# Mini_Keyboard_EasyEDA.net
KiCad netlist of a schematic drawn in EasyEDA
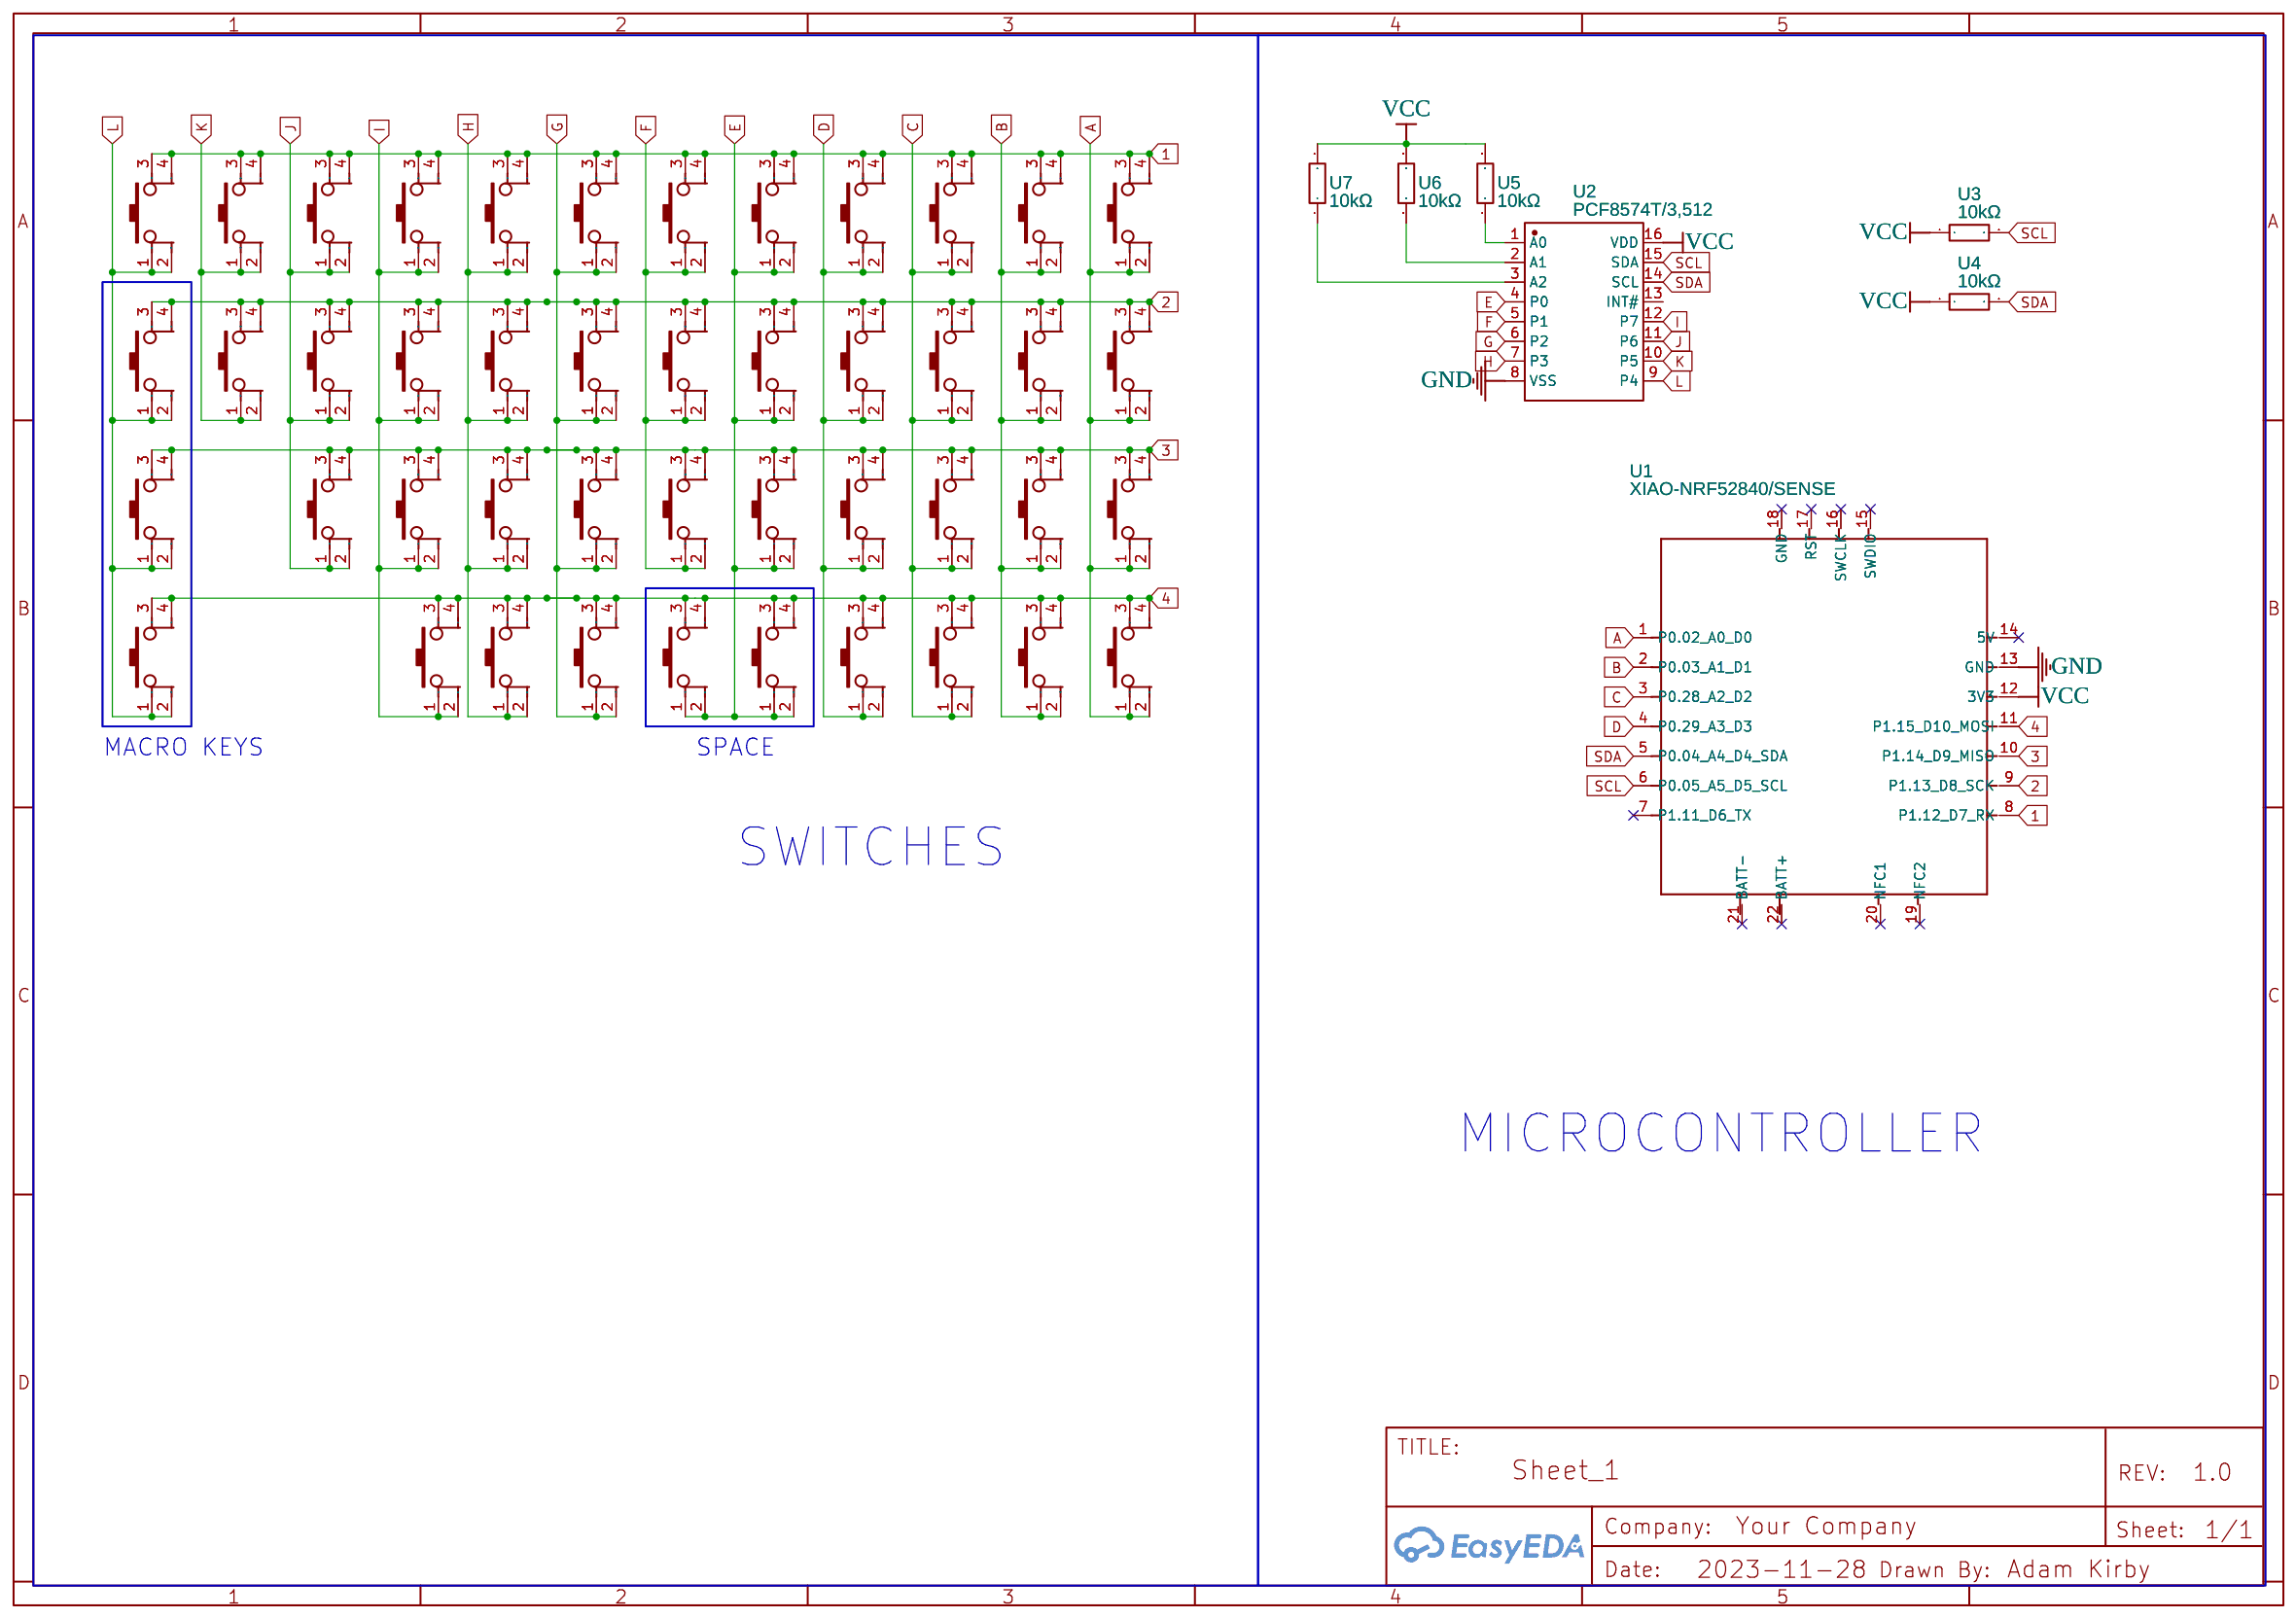
[diagram p0: schematic sheet]

(export (version "E")
  (design (tool "Eeschema 10.0.6"))
  (components
    (comp (ref "ESC")
      (value "Switch-SMD-6x6x11")
      (fields (field (name "Manufacturer Part") "Switch6*6*11") (field (name "Manufacturer") "BBJ"))
      (libsource (lib "") (part "Switch-SMD-6x6x11_1"))
    )
    (comp (ref "MAC1")
      (value "Switch-SMD-6x6x11")
      (fields (field (name "Manufacturer Part") "Switch6*6*11") (field (name "Manufacturer") "BBJ"))
      (libsource (lib "") (part "Switch-SMD-6x6x11_2"))
    )
    (comp (ref "MAC2")
      (value "Switch-SMD-6x6x11")
      (fields (field (name "Manufacturer Part") "Switch6*6*11") (field (name "Manufacturer") "BBJ"))
      (libsource (lib "") (part "Switch-SMD-6x6x11_2"))
    )
    (comp (ref "MAC3")
      (value "Switch-SMD-6x6x11")
      (fields (field (name "Manufacturer Part") "Switch6*6*11") (field (name "Manufacturer") "BBJ"))
      (libsource (lib "") (part "Switch-SMD-6x6x11_2"))
    )
    (comp (ref "SW1")
      (value "Switch-SMD-6x6x11")
      (fields (field (name "Manufacturer Part") "Switch6*6*11") (field (name "Manufacturer") "BBJ"))
      (libsource (lib "") (part "Switch-SMD-6x6x11"))
    )
    (comp (ref "SW2")
      (value "Switch-SMD-6x6x11")
      (fields (field (name "Manufacturer Part") "Switch6*6*11") (field (name "Manufacturer") "BBJ"))
      (libsource (lib "") (part "Switch-SMD-6x6x11"))
    )
    (comp (ref "SW3")
      (value "Switch-SMD-6x6x11")
      (fields (field (name "Manufacturer Part") "Switch6*6*11") (field (name "Manufacturer") "BBJ"))
      (libsource (lib "") (part "Switch-SMD-6x6x11"))
    )
    (comp (ref "SW4")
      (value "Switch-SMD-6x6x11")
      (fields (field (name "Manufacturer Part") "Switch6*6*11") (field (name "Manufacturer") "BBJ"))
      (libsource (lib "") (part "Switch-SMD-6x6x11"))
    )
    (comp (ref "SW5")
      (value "Switch-SMD-6x6x11")
      (fields (field (name "Manufacturer Part") "Switch6*6*11") (field (name "Manufacturer") "BBJ"))
      (libsource (lib "") (part "Switch-SMD-6x6x11"))
    )
    (comp (ref "SW6")
      (value "Switch-SMD-6x6x11")
      (fields (field (name "Manufacturer Part") "Switch6*6*11") (field (name "Manufacturer") "BBJ"))
      (libsource (lib "") (part "Switch-SMD-6x6x11"))
    )
    (comp (ref "SW7")
      (value "Switch-SMD-6x6x11")
      (fields (field (name "Manufacturer Part") "Switch6*6*11") (field (name "Manufacturer") "BBJ"))
      (libsource (lib "") (part "Switch-SMD-6x6x11"))
    )
    (comp (ref "SW8")
      (value "Switch-SMD-6x6x11")
      (fields (field (name "Manufacturer Part") "Switch6*6*11") (field (name "Manufacturer") "BBJ"))
      (libsource (lib "") (part "Switch-SMD-6x6x11"))
    )
    (comp (ref "SW9")
      (value "Switch-SMD-6x6x11")
      (fields (field (name "Manufacturer Part") "Switch6*6*11") (field (name "Manufacturer") "BBJ"))
      (libsource (lib "") (part "Switch-SMD-6x6x11"))
    )
    (comp (ref "SW10")
      (value "Switch-SMD-6x6x11")
      (fields (field (name "Manufacturer Part") "Switch6*6*11") (field (name "Manufacturer") "BBJ"))
      (libsource (lib "") (part "Switch-SMD-6x6x11"))
    )
    (comp (ref "SW11")
      (value "Switch-SMD-6x6x11")
      (fields (field (name "Manufacturer Part") "Switch6*6*11") (field (name "Manufacturer") "BBJ"))
      (libsource (lib "") (part "Switch-SMD-6x6x11"))
    )
    (comp (ref "SW12")
      (value "Switch-SMD-6x6x11")
      (fields (field (name "Manufacturer Part") "Switch6*6*11") (field (name "Manufacturer") "BBJ"))
      (libsource (lib "") (part "Switch-SMD-6x6x11"))
    )
    (comp (ref "SW13")
      (value "Switch-SMD-6x6x11")
      (fields (field (name "Manufacturer Part") "Switch6*6*11") (field (name "Manufacturer") "BBJ"))
      (libsource (lib "") (part "Switch-SMD-6x6x11"))
    )
    (comp (ref "SW14")
      (value "Switch-SMD-6x6x11")
      (fields (field (name "Manufacturer Part") "Switch6*6*11") (field (name "Manufacturer") "BBJ"))
      (libsource (lib "") (part "Switch-SMD-6x6x11"))
    )
    (comp (ref "SW15")
      (value "Switch-SMD-6x6x11")
      (fields (field (name "Manufacturer Part") "Switch6*6*11") (field (name "Manufacturer") "BBJ"))
      (libsource (lib "") (part "Switch-SMD-6x6x11"))
    )
    (comp (ref "SW16")
      (value "Switch-SMD-6x6x11")
      (fields (field (name "Manufacturer Part") "Switch6*6*11") (field (name "Manufacturer") "BBJ"))
      (libsource (lib "") (part "Switch-SMD-6x6x11"))
    )
    (comp (ref "SW17")
      (value "Switch-SMD-6x6x11")
      (fields (field (name "Manufacturer Part") "Switch6*6*11") (field (name "Manufacturer") "BBJ"))
      (libsource (lib "") (part "Switch-SMD-6x6x11"))
    )
    (comp (ref "SW18")
      (value "Switch-SMD-6x6x11")
      (fields (field (name "Manufacturer Part") "Switch6*6*11") (field (name "Manufacturer") "BBJ"))
      (libsource (lib "") (part "Switch-SMD-6x6x11"))
    )
    (comp (ref "SW19")
      (value "Switch-SMD-6x6x11")
      (fields (field (name "Manufacturer Part") "Switch6*6*11") (field (name "Manufacturer") "BBJ"))
      (libsource (lib "") (part "Switch-SMD-6x6x11"))
    )
    (comp (ref "SW20")
      (value "Switch-SMD-6x6x11")
      (fields (field (name "Manufacturer Part") "Switch6*6*11") (field (name "Manufacturer") "BBJ"))
      (libsource (lib "") (part "Switch-SMD-6x6x11"))
    )
    (comp (ref "SW21")
      (value "Switch-SMD-6x6x11")
      (fields (field (name "Manufacturer Part") "Switch6*6*11") (field (name "Manufacturer") "BBJ"))
      (libsource (lib "") (part "Switch-SMD-6x6x11"))
    )
    (comp (ref "SW22")
      (value "Switch-SMD-6x6x11")
      (fields (field (name "Manufacturer Part") "Switch6*6*11") (field (name "Manufacturer") "BBJ"))
      (libsource (lib "") (part "Switch-SMD-6x6x11"))
    )
    (comp (ref "SW23")
      (value "Switch-SMD-6x6x11")
      (fields (field (name "Manufacturer Part") "Switch6*6*11") (field (name "Manufacturer") "BBJ"))
      (libsource (lib "") (part "Switch-SMD-6x6x11"))
    )
    (comp (ref "SW24")
      (value "Switch-SMD-6x6x11")
      (fields (field (name "Manufacturer Part") "Switch6*6*11") (field (name "Manufacturer") "BBJ"))
      (libsource (lib "") (part "Switch-SMD-6x6x11"))
    )
    (comp (ref "SW25")
      (value "Switch-SMD-6x6x11")
      (fields (field (name "Manufacturer Part") "Switch6*6*11") (field (name "Manufacturer") "BBJ"))
      (libsource (lib "") (part "Switch-SMD-6x6x11"))
    )
    (comp (ref "SW27")
      (value "Switch-SMD-6x6x11")
      (fields (field (name "Manufacturer Part") "Switch6*6*11") (field (name "Manufacturer") "BBJ"))
      (libsource (lib "") (part "Switch-SMD-6x6x11"))
    )
    (comp (ref "SW28")
      (value "Switch-SMD-6x6x11")
      (fields (field (name "Manufacturer Part") "Switch6*6*11") (field (name "Manufacturer") "BBJ"))
      (libsource (lib "") (part "Switch-SMD-6x6x11"))
    )
    (comp (ref "SW29")
      (value "Switch-SMD-6x6x11")
      (fields (field (name "Manufacturer Part") "Switch6*6*11") (field (name "Manufacturer") "BBJ"))
      (libsource (lib "") (part "Switch-SMD-6x6x11"))
    )
    (comp (ref "SW30")
      (value "Switch-SMD-6x6x11")
      (fields (field (name "Manufacturer Part") "Switch6*6*11") (field (name "Manufacturer") "BBJ"))
      (libsource (lib "") (part "Switch-SMD-6x6x11"))
    )
    (comp (ref "SW31")
      (value "Switch-SMD-6x6x11")
      (fields (field (name "Manufacturer Part") "Switch6*6*11") (field (name "Manufacturer") "BBJ"))
      (libsource (lib "") (part "Switch-SMD-6x6x11"))
    )
    (comp (ref "SW32")
      (value "Switch-SMD-6x6x11")
      (fields (field (name "Manufacturer Part") "Switch6*6*11") (field (name "Manufacturer") "BBJ"))
      (libsource (lib "") (part "Switch-SMD-6x6x11"))
    )
    (comp (ref "SW33")
      (value "Switch-SMD-6x6x11")
      (fields (field (name "Manufacturer Part") "Switch6*6*11") (field (name "Manufacturer") "BBJ"))
      (libsource (lib "") (part "Switch-SMD-6x6x11"))
    )
    (comp (ref "SW34")
      (value "Switch-SMD-6x6x11")
      (fields (field (name "Manufacturer Part") "Switch6*6*11") (field (name "Manufacturer") "BBJ"))
      (libsource (lib "") (part "Switch-SMD-6x6x11"))
    )
    (comp (ref "SW35")
      (value "Switch-SMD-6x6x11")
      (fields (field (name "Manufacturer Part") "Switch6*6*11") (field (name "Manufacturer") "BBJ"))
      (libsource (lib "") (part "Switch-SMD-6x6x11"))
    )
    (comp (ref "SW43")
      (value "Switch-SMD-6x6x11")
      (fields (field (name "Manufacturer Part") "Switch6*6*11") (field (name "Manufacturer") "BBJ"))
      (libsource (lib "") (part "Switch-SMD-6x6x11"))
    )
    (comp (ref "SW44")
      (value "Switch-SMD-6x6x11")
      (fields (field (name "Manufacturer Part") "Switch6*6*11") (field (name "Manufacturer") "BBJ"))
      (libsource (lib "") (part "Switch-SMD-6x6x11"))
    )
    (comp (ref "SW45")
      (value "Switch-SMD-6x6x11")
      (fields (field (name "Manufacturer Part") "Switch6*6*11") (field (name "Manufacturer") "BBJ"))
      (libsource (lib "") (part "Switch-SMD-6x6x11"))
    )
    (comp (ref "SW46")
      (value "Switch-SMD-6x6x11")
      (fields (field (name "Manufacturer Part") "Switch6*6*11") (field (name "Manufacturer") "BBJ"))
      (libsource (lib "") (part "Switch-SMD-6x6x11"))
    )
    (comp (ref "SW47")
      (value "Switch-SMD-6x6x11")
      (fields (field (name "Manufacturer Part") "Switch6*6*11") (field (name "Manufacturer") "BBJ"))
      (libsource (lib "") (part "Switch-SMD-6x6x11"))
    )
    (comp (ref "SW48")
      (value "Switch-SMD-6x6x11")
      (fields (field (name "Manufacturer Part") "Switch6*6*11") (field (name "Manufacturer") "BBJ"))
      (libsource (lib "") (part "Switch-SMD-6x6x11"))
    )
    (comp (ref "SW49")
      (value "Switch-SMD-6x6x11")
      (fields (field (name "Manufacturer Part") "Switch6*6*11") (field (name "Manufacturer") "BBJ"))
      (libsource (lib "") (part "Switch-SMD-6x6x11"))
    )
    (comp (ref "U1") (value "XIAO-NRF52840/SENSE") (libsource (lib "") (part "XIAO-NRF52840/SENSE")))
    (comp (ref "U2")
      (value "PCF8574T/3,512")
      (fields (field (name "Manufacturer") "NXP(恩智浦)"))
      (libsource (lib "") (part "PCF8574T/3,512"))
    )
    (comp (ref "U3")
      (value "10kΩ")
      (fields
        (field (name "Manufacturer Part") "RNCF0805TKW10K0")
        (field (name "Manufacturer") "SEI(Stackpole Electronics Inc.)")
      )
      (libsource (lib "") (part "RNCF0805TKW10K0"))
    )
    (comp (ref "U4")
      (value "10kΩ")
      (fields
        (field (name "Manufacturer Part") "RNCF0805TKW10K0")
        (field (name "Manufacturer") "SEI(Stackpole Electronics Inc.)")
      )
      (libsource (lib "") (part "RNCF0805TKW10K0"))
    )
    (comp (ref "U5")
      (value "10kΩ")
      (fields
        (field (name "Manufacturer Part") "RNCF0805TKW10K0")
        (field (name "Manufacturer") "SEI(Stackpole Electronics Inc.)")
      )
      (libsource (lib "") (part "RNCF0805TKW10K0_1"))
    )
    (comp (ref "U6")
      (value "10kΩ")
      (fields
        (field (name "Manufacturer Part") "RNCF0805TKW10K0")
        (field (name "Manufacturer") "SEI(Stackpole Electronics Inc.)")
      )
      (libsource (lib "") (part "RNCF0805TKW10K0_1"))
    )
    (comp (ref "U7")
      (value "10kΩ")
      (fields
        (field (name "Manufacturer Part") "RNCF0805TKW10K0")
        (field (name "Manufacturer") "SEI(Stackpole Electronics Inc.)")
      )
      (libsource (lib "") (part "RNCF0805TKW10K0_1"))
    )
  )
  (nets
    (net (code "1") (name "1") (class "Default")
      (node (ref "SW1") (pin "3") (pinfunction "3_3") (pintype "input"))
      (node (ref "SW1") (pin "4") (pinfunction "4_4") (pintype "input"))
      (node (ref "SW10") (pin "3") (pinfunction "3_3") (pintype "input"))
      (node (ref "SW10") (pin "4") (pinfunction "4_4") (pintype "input"))
      (node (ref "SW11") (pin "3") (pinfunction "3_3") (pintype "input"))
      (node (ref "SW11") (pin "4") (pinfunction "4_4") (pintype "input"))
      (node (ref "SW12") (pin "3") (pinfunction "3_3") (pintype "input"))
      (node (ref "SW12") (pin "4") (pinfunction "4_4") (pintype "input"))
      (node (ref "SW2") (pin "3") (pinfunction "3_3") (pintype "input"))
      (node (ref "SW2") (pin "4") (pinfunction "4_4") (pintype "input"))
      (node (ref "SW3") (pin "3") (pinfunction "3_3") (pintype "input"))
      (node (ref "SW3") (pin "4") (pinfunction "4_4") (pintype "input"))
      (node (ref "SW4") (pin "3") (pinfunction "3_3") (pintype "input"))
      (node (ref "SW4") (pin "4") (pinfunction "4_4") (pintype "input"))
      (node (ref "SW5") (pin "3") (pinfunction "3_3") (pintype "input"))
      (node (ref "SW5") (pin "4") (pinfunction "4_4") (pintype "input"))
      (node (ref "SW6") (pin "3") (pinfunction "3_3") (pintype "input"))
      (node (ref "SW6") (pin "4") (pinfunction "4_4") (pintype "input"))
      (node (ref "SW7") (pin "3") (pinfunction "3_3") (pintype "input"))
      (node (ref "SW7") (pin "4") (pinfunction "4_4") (pintype "input"))
      (node (ref "SW8") (pin "3") (pinfunction "3_3") (pintype "input"))
      (node (ref "SW8") (pin "4") (pinfunction "4_4") (pintype "input"))
      (node (ref "SW9") (pin "3") (pinfunction "3_3") (pintype "input"))
      (node (ref "SW9") (pin "4") (pinfunction "4_4") (pintype "input"))
      (node (ref "U1") (pin "8") (pinfunction "P1.12_D7_RX_8") (pintype "bidirectional"))
    )
    (net (code "2") (name "2") (class "Default")
      (node (ref "MAC1") (pin "3") (pinfunction "3_3") (pintype "input"))
      (node (ref "MAC1") (pin "4") (pinfunction "4_4") (pintype "input"))
      (node (ref "SW13") (pin "3") (pinfunction "3_3") (pintype "input"))
      (node (ref "SW13") (pin "4") (pinfunction "4_4") (pintype "input"))
      (node (ref "SW14") (pin "3") (pinfunction "3_3") (pintype "input"))
      (node (ref "SW14") (pin "4") (pinfunction "4_4") (pintype "input"))
      (node (ref "SW15") (pin "3") (pinfunction "3_3") (pintype "input"))
      (node (ref "SW15") (pin "4") (pinfunction "4_4") (pintype "input"))
      (node (ref "SW16") (pin "3") (pinfunction "3_3") (pintype "input"))
      (node (ref "SW16") (pin "4") (pinfunction "4_4") (pintype "input"))
      (node (ref "SW17") (pin "3") (pinfunction "3_3") (pintype "input"))
      (node (ref "SW17") (pin "4") (pinfunction "4_4") (pintype "input"))
      (node (ref "SW18") (pin "3") (pinfunction "3_3") (pintype "input"))
      (node (ref "SW18") (pin "4") (pinfunction "4_4") (pintype "input"))
      (node (ref "SW19") (pin "3") (pinfunction "3_3") (pintype "input"))
      (node (ref "SW19") (pin "4") (pinfunction "4_4") (pintype "input"))
      (node (ref "SW20") (pin "3") (pinfunction "3_3") (pintype "input"))
      (node (ref "SW20") (pin "4") (pinfunction "4_4") (pintype "input"))
      (node (ref "SW21") (pin "3") (pinfunction "3_3") (pintype "input"))
      (node (ref "SW21") (pin "4") (pinfunction "4_4") (pintype "input"))
      (node (ref "SW22") (pin "3") (pinfunction "3_3") (pintype "input"))
      (node (ref "SW22") (pin "4") (pinfunction "4_4") (pintype "input"))
      (node (ref "SW23") (pin "3") (pinfunction "3_3") (pintype "input"))
      (node (ref "SW23") (pin "4") (pinfunction "4_4") (pintype "input"))
      (node (ref "U1") (pin "9") (pinfunction "P1.13_D8_SCK_9") (pintype "bidirectional"))
    )
    (net (code "3") (name "3") (class "Default")
      (node (ref "ESC") (pin "3") (pinfunction "3_3") (pintype "input"))
      (node (ref "ESC") (pin "4") (pinfunction "4_4") (pintype "input"))
      (node (ref "MAC2") (pin "3") (pinfunction "3_3") (pintype "input"))
      (node (ref "MAC2") (pin "4") (pinfunction "4_4") (pintype "input"))
      (node (ref "SW24") (pin "3") (pinfunction "3_3") (pintype "input"))
      (node (ref "SW24") (pin "4") (pinfunction "4_4") (pintype "input"))
      (node (ref "SW25") (pin "3") (pinfunction "3_3") (pintype "input"))
      (node (ref "SW25") (pin "4") (pinfunction "4_4") (pintype "input"))
      (node (ref "SW43") (pin "3") (pinfunction "3_3") (pintype "input"))
      (node (ref "SW43") (pin "4") (pinfunction "4_4") (pintype "input"))
      (node (ref "SW44") (pin "3") (pinfunction "3_3") (pintype "input"))
      (node (ref "SW44") (pin "4") (pinfunction "4_4") (pintype "input"))
      (node (ref "SW45") (pin "3") (pinfunction "3_3") (pintype "input"))
      (node (ref "SW45") (pin "4") (pinfunction "4_4") (pintype "input"))
      (node (ref "SW46") (pin "3") (pinfunction "3_3") (pintype "input"))
      (node (ref "SW46") (pin "4") (pinfunction "4_4") (pintype "input"))
      (node (ref "SW47") (pin "3") (pinfunction "3_3") (pintype "input"))
      (node (ref "SW47") (pin "4") (pinfunction "4_4") (pintype "input"))
      (node (ref "SW48") (pin "3") (pinfunction "3_3") (pintype "input"))
      (node (ref "SW48") (pin "4") (pinfunction "4_4") (pintype "input"))
      (node (ref "SW49") (pin "3") (pinfunction "3_3") (pintype "input"))
      (node (ref "SW49") (pin "4") (pinfunction "4_4") (pintype "input"))
      (node (ref "U1") (pin "10") (pinfunction "P1.14_D9_MISO_10") (pintype "bidirectional"))
    )
    (net (code "4") (name "4") (class "Default")
      (node (ref "MAC3") (pin "3") (pinfunction "3_3") (pintype "input"))
      (node (ref "MAC3") (pin "4") (pinfunction "4_4") (pintype "input"))
      (node (ref "SW27") (pin "3") (pinfunction "3_3") (pintype "input"))
      (node (ref "SW27") (pin "4") (pinfunction "4_4") (pintype "input"))
      (node (ref "SW28") (pin "3") (pinfunction "3_3") (pintype "input"))
      (node (ref "SW28") (pin "4") (pinfunction "4_4") (pintype "input"))
      (node (ref "SW29") (pin "3") (pinfunction "3_3") (pintype "input"))
      (node (ref "SW29") (pin "4") (pinfunction "4_4") (pintype "input"))
      (node (ref "SW30") (pin "3") (pinfunction "3_3") (pintype "input"))
      (node (ref "SW30") (pin "4") (pinfunction "4_4") (pintype "input"))
      (node (ref "SW31") (pin "3") (pinfunction "3_3") (pintype "input"))
      (node (ref "SW31") (pin "4") (pinfunction "4_4") (pintype "input"))
      (node (ref "SW32") (pin "3") (pinfunction "3_3") (pintype "input"))
      (node (ref "SW32") (pin "4") (pinfunction "4_4") (pintype "input"))
      (node (ref "SW33") (pin "3") (pinfunction "3_3") (pintype "input"))
      (node (ref "SW33") (pin "4") (pinfunction "4_4") (pintype "input"))
      (node (ref "SW34") (pin "3") (pinfunction "3_3") (pintype "input"))
      (node (ref "SW34") (pin "4") (pinfunction "4_4") (pintype "input"))
      (node (ref "SW35") (pin "3") (pinfunction "3_3") (pintype "input"))
      (node (ref "SW35") (pin "4") (pinfunction "4_4") (pintype "input"))
      (node (ref "U1") (pin "11") (pinfunction "P1.15_D10_MOSI_11") (pintype "bidirectional"))
    )
    (net (code "5") (name "A") (class "Default")
      (node (ref "ESC") (pin "1") (pinfunction "1_1") (pintype "input"))
      (node (ref "ESC") (pin "2") (pinfunction "2_2") (pintype "input"))
      (node (ref "SW10") (pin "1") (pinfunction "1_1") (pintype "input"))
      (node (ref "SW10") (pin "2") (pinfunction "2_2") (pintype "input"))
      (node (ref "SW13") (pin "1") (pinfunction "1_1") (pintype "input"))
      (node (ref "SW13") (pin "2") (pinfunction "2_2") (pintype "input"))
      (node (ref "SW27") (pin "1") (pinfunction "1_1") (pintype "input"))
      (node (ref "SW27") (pin "2") (pinfunction "2_2") (pintype "input"))
      (node (ref "U1") (pin "1") (pinfunction "P0.02_A0_D0_1") (pintype "bidirectional"))
    )
    (net (code "6") (name "B") (class "Default")
      (node (ref "SW11") (pin "1") (pinfunction "1_1") (pintype "input"))
      (node (ref "SW11") (pin "2") (pinfunction "2_2") (pintype "input"))
      (node (ref "SW15") (pin "1") (pinfunction "1_1") (pintype "input"))
      (node (ref "SW15") (pin "2") (pinfunction "2_2") (pintype "input"))
      (node (ref "SW24") (pin "1") (pinfunction "1_1") (pintype "input"))
      (node (ref "SW24") (pin "2") (pinfunction "2_2") (pintype "input"))
      (node (ref "SW29") (pin "1") (pinfunction "1_1") (pintype "input"))
      (node (ref "SW29") (pin "2") (pinfunction "2_2") (pintype "input"))
      (node (ref "U1") (pin "2") (pinfunction "P0.03_A1_D1_2") (pintype "bidirectional"))
    )
    (net (code "7") (name "C") (class "Default")
      (node (ref "SW12") (pin "1") (pinfunction "1_1") (pintype "input"))
      (node (ref "SW12") (pin "2") (pinfunction "2_2") (pintype "input"))
      (node (ref "SW14") (pin "1") (pinfunction "1_1") (pintype "input"))
      (node (ref "SW14") (pin "2") (pinfunction "2_2") (pintype "input"))
      (node (ref "SW25") (pin "1") (pinfunction "1_1") (pintype "input"))
      (node (ref "SW25") (pin "2") (pinfunction "2_2") (pintype "input"))
      (node (ref "SW28") (pin "1") (pinfunction "1_1") (pintype "input"))
      (node (ref "SW28") (pin "2") (pinfunction "2_2") (pintype "input"))
      (node (ref "U1") (pin "3") (pinfunction "P0.28_A2_D2_3") (pintype "bidirectional"))
    )
    (net (code "8") (name "D") (class "Default")
      (node (ref "SW18") (pin "1") (pinfunction "1_1") (pintype "input"))
      (node (ref "SW18") (pin "2") (pinfunction "2_2") (pintype "input"))
      (node (ref "SW32") (pin "1") (pinfunction "1_1") (pintype "input"))
      (node (ref "SW32") (pin "2") (pinfunction "2_2") (pintype "input"))
      (node (ref "SW45") (pin "1") (pinfunction "1_1") (pintype "input"))
      (node (ref "SW45") (pin "2") (pinfunction "2_2") (pintype "input"))
      (node (ref "SW7") (pin "1") (pinfunction "1_1") (pintype "input"))
      (node (ref "SW7") (pin "2") (pinfunction "2_2") (pintype "input"))
      (node (ref "U1") (pin "4") (pinfunction "P0.29_A3_D3_4") (pintype "bidirectional"))
    )
    (net (code "9") (name "E") (class "Default")
      (node (ref "SW17") (pin "1") (pinfunction "1_1") (pintype "input"))
      (node (ref "SW17") (pin "2") (pinfunction "2_2") (pintype "input"))
      (node (ref "SW30") (pin "1") (pinfunction "1_1") (pintype "input"))
      (node (ref "SW30") (pin "2") (pinfunction "2_2") (pintype "input"))
      (node (ref "SW31") (pin "1") (pinfunction "1_1") (pintype "input"))
      (node (ref "SW31") (pin "2") (pinfunction "2_2") (pintype "input"))
      (node (ref "SW44") (pin "1") (pinfunction "1_1") (pintype "input"))
      (node (ref "SW44") (pin "2") (pinfunction "2_2") (pintype "input"))
      (node (ref "SW8") (pin "1") (pinfunction "1_1") (pintype "input"))
      (node (ref "SW8") (pin "2") (pinfunction "2_2") (pintype "input"))
      (node (ref "U2") (pin "4") (pinfunction "P0_4") (pintype "unspecified"))
    )
    (net (code "10") (name "F") (class "Default")
      (node (ref "SW16") (pin "1") (pinfunction "1_1") (pintype "input"))
      (node (ref "SW16") (pin "2") (pinfunction "2_2") (pintype "input"))
      (node (ref "SW43") (pin "1") (pinfunction "1_1") (pintype "input"))
      (node (ref "SW43") (pin "2") (pinfunction "2_2") (pintype "input"))
      (node (ref "SW9") (pin "1") (pinfunction "1_1") (pintype "input"))
      (node (ref "SW9") (pin "2") (pinfunction "2_2") (pintype "input"))
      (node (ref "U2") (pin "5") (pinfunction "P1_5") (pintype "unspecified"))
    )
    (net (code "11") (name "G") (class "Default")
      (node (ref "SW21") (pin "1") (pinfunction "1_1") (pintype "input"))
      (node (ref "SW21") (pin "2") (pinfunction "2_2") (pintype "input"))
      (node (ref "SW35") (pin "1") (pinfunction "1_1") (pintype "input"))
      (node (ref "SW35") (pin "2") (pinfunction "2_2") (pintype "input"))
      (node (ref "SW4") (pin "1") (pinfunction "1_1") (pintype "input"))
      (node (ref "SW4") (pin "2") (pinfunction "2_2") (pintype "input"))
      (node (ref "SW48") (pin "1") (pinfunction "1_1") (pintype "input"))
      (node (ref "SW48") (pin "2") (pinfunction "2_2") (pintype "input"))
      (node (ref "U2") (pin "6") (pinfunction "P2_6") (pintype "unspecified"))
    )
    (net (code "12") (name "GND") (class "Default")
      (node (ref "U1") (pin "13") (pinfunction "GND_13") (pintype "bidirectional"))
      (node (ref "U2") (pin "8") (pinfunction "VSS_8") (pintype "unspecified"))
    )
    (net (code "13") (name "H") (class "Default")
      (node (ref "SW20") (pin "1") (pinfunction "1_1") (pintype "input"))
      (node (ref "SW20") (pin "2") (pinfunction "2_2") (pintype "input"))
      (node (ref "SW34") (pin "1") (pinfunction "1_1") (pintype "input"))
      (node (ref "SW34") (pin "2") (pinfunction "2_2") (pintype "input"))
      (node (ref "SW47") (pin "1") (pinfunction "1_1") (pintype "input"))
      (node (ref "SW47") (pin "2") (pinfunction "2_2") (pintype "input"))
      (node (ref "SW5") (pin "1") (pinfunction "1_1") (pintype "input"))
      (node (ref "SW5") (pin "2") (pinfunction "2_2") (pintype "input"))
      (node (ref "U2") (pin "7") (pinfunction "P3_7") (pintype "unspecified"))
    )
    (net (code "14") (name "I") (class "Default")
      (node (ref "SW19") (pin "1") (pinfunction "1_1") (pintype "input"))
      (node (ref "SW19") (pin "2") (pinfunction "2_2") (pintype "input"))
      (node (ref "SW33") (pin "1") (pinfunction "1_1") (pintype "input"))
      (node (ref "SW33") (pin "2") (pinfunction "2_2") (pintype "input"))
      (node (ref "SW46") (pin "1") (pinfunction "1_1") (pintype "input"))
      (node (ref "SW46") (pin "2") (pinfunction "2_2") (pintype "input"))
      (node (ref "SW6") (pin "1") (pinfunction "1_1") (pintype "input"))
      (node (ref "SW6") (pin "2") (pinfunction "2_2") (pintype "input"))
      (node (ref "U2") (pin "12") (pinfunction "P7_12") (pintype "unspecified"))
    )
    (net (code "15") (name "J") (class "Default")
      (node (ref "SW22") (pin "1") (pinfunction "1_1") (pintype "input"))
      (node (ref "SW22") (pin "2") (pinfunction "2_2") (pintype "input"))
      (node (ref "SW3") (pin "1") (pinfunction "1_1") (pintype "input"))
      (node (ref "SW3") (pin "2") (pinfunction "2_2") (pintype "input"))
      (node (ref "SW49") (pin "1") (pinfunction "1_1") (pintype "input"))
      (node (ref "SW49") (pin "2") (pinfunction "2_2") (pintype "input"))
      (node (ref "U2") (pin "11") (pinfunction "P6_11") (pintype "unspecified"))
    )
    (net (code "16") (name "K") (class "Default")
      (node (ref "SW2") (pin "1") (pinfunction "1_1") (pintype "input"))
      (node (ref "SW2") (pin "2") (pinfunction "2_2") (pintype "input"))
      (node (ref "SW23") (pin "1") (pinfunction "1_1") (pintype "input"))
      (node (ref "SW23") (pin "2") (pinfunction "2_2") (pintype "input"))
      (node (ref "U2") (pin "10") (pinfunction "P5_10") (pintype "unspecified"))
    )
    (net (code "17") (name "L") (class "Default")
      (node (ref "MAC1") (pin "1") (pinfunction "1_1") (pintype "input"))
      (node (ref "MAC1") (pin "2") (pinfunction "2_2") (pintype "input"))
      (node (ref "MAC2") (pin "1") (pinfunction "1_1") (pintype "input"))
      (node (ref "MAC2") (pin "2") (pinfunction "2_2") (pintype "input"))
      (node (ref "MAC3") (pin "1") (pinfunction "1_1") (pintype "input"))
      (node (ref "MAC3") (pin "2") (pinfunction "2_2") (pintype "input"))
      (node (ref "SW1") (pin "1") (pinfunction "1_1") (pintype "input"))
      (node (ref "SW1") (pin "2") (pinfunction "2_2") (pintype "input"))
      (node (ref "U2") (pin "9") (pinfunction "P4_9") (pintype "unspecified"))
    )
    (net (code "18") (name "Net-(U2-A0)") (class "Default")
      (node (ref "U2") (pin "1") (pinfunction "A0_1") (pintype "unspecified"))
      (node (ref "U5") (pin "1") (pinfunction "1_1") (pintype "unspecified"))
    )
    (net (code "19") (name "Net-(U2-A1)") (class "Default")
      (node (ref "U2") (pin "2") (pinfunction "A1_2") (pintype "unspecified"))
      (node (ref "U6") (pin "1") (pinfunction "1_1") (pintype "unspecified"))
    )
    (net (code "20") (name "Net-(U2-A2)") (class "Default")
      (node (ref "U2") (pin "3") (pinfunction "A2_3") (pintype "unspecified"))
      (node (ref "U7") (pin "1") (pinfunction "1_1") (pintype "unspecified"))
    )
    (net (code "21") (name "SCL") (class "Default")
      (node (ref "U1") (pin "6") (pinfunction "P0.05_A5_D5_SCL_6") (pintype "bidirectional"))
      (node (ref "U2") (pin "15") (pinfunction "SDA_15") (pintype "unspecified"))
      (node (ref "U3") (pin "2") (pinfunction "2_2") (pintype "unspecified"))
    )
    (net (code "22") (name "SDA") (class "Default")
      (node (ref "U1") (pin "5") (pinfunction "P0.04_A4_D4_SDA_5") (pintype "bidirectional"))
      (node (ref "U2") (pin "14") (pinfunction "SCL_14") (pintype "unspecified"))
      (node (ref "U4") (pin "2") (pinfunction "2_2") (pintype "unspecified"))
    )
    (net (code "23") (name "VCC") (class "Default")
      (node (ref "U1") (pin "12") (pinfunction "3V3_12") (pintype "bidirectional"))
      (node (ref "U2") (pin "16") (pinfunction "VDD_16") (pintype "unspecified"))
      (node (ref "U3") (pin "1") (pinfunction "1_1") (pintype "unspecified"))
      (node (ref "U4") (pin "1") (pinfunction "1_1") (pintype "unspecified"))
      (node (ref "U5") (pin "2") (pinfunction "2_2") (pintype "unspecified"))
      (node (ref "U6") (pin "2") (pinfunction "2_2") (pintype "unspecified"))
      (node (ref "U7") (pin "2") (pinfunction "2_2") (pintype "unspecified"))
    )
    (net (code "24") (name "unconnected-(U1-5V-Pad14)") (class "Default")
      (node (ref "U1") (pin "14") (pinfunction "5V_14") (pintype "bidirectional+no_connect"))
    )
    (net (code "25") (name "unconnected-(U1-BATT+-Pad22)") (class "Default")
      (node (ref "U1") (pin "22") (pinfunction "BATT+_22") (pintype "bidirectional+no_connect"))
    )
    (net (code "26") (name "unconnected-(U1-BATT--Pad21)") (class "Default")
      (node (ref "U1") (pin "21") (pinfunction "BATT-_21") (pintype "bidirectional+no_connect"))
    )
    (net (code "27") (name "unconnected-(U1-GND-Pad18)") (class "Default")
      (node (ref "U1") (pin "18") (pinfunction "GND_18") (pintype "bidirectional+no_connect"))
    )
    (net (code "28") (name "unconnected-(U1-NFC1-Pad20)") (class "Default")
      (node (ref "U1") (pin "20") (pinfunction "NFC1_20") (pintype "bidirectional+no_connect"))
    )
    (net (code "29") (name "unconnected-(U1-NFC2-Pad19)") (class "Default")
      (node (ref "U1") (pin "19") (pinfunction "NFC2_19") (pintype "bidirectional+no_connect"))
    )
    (net (code "30") (name "unconnected-(U1-P1.11_D6_TX-Pad7)") (class "Default")
      (node (ref "U1") (pin "7") (pinfunction "P1.11_D6_TX_7") (pintype "bidirectional+no_connect"))
    )
    (net (code "31") (name "unconnected-(U1-RST-Pad17)") (class "Default")
      (node (ref "U1") (pin "17") (pinfunction "RST_17") (pintype "bidirectional+no_connect"))
    )
    (net (code "32") (name "unconnected-(U1-SWCLK-Pad16)") (class "Default")
      (node (ref "U1") (pin "16") (pinfunction "SWCLK_16") (pintype "bidirectional+no_connect"))
    )
    (net (code "33") (name "unconnected-(U1-SWDIO-Pad15)") (class "Default")
      (node (ref "U1") (pin "15") (pinfunction "SWDIO_15") (pintype "bidirectional+no_connect"))
    )
    (net (code "34") (name "unconnected-(U2-INT#-Pad13)") (class "Default")
      (node (ref "U2") (pin "13") (pinfunction "INT#_13") (pintype "unspecified"))
    )
  )
)
